# Heater_Driver.net
KiCad netlist of a schematic drawn in Altium Designer
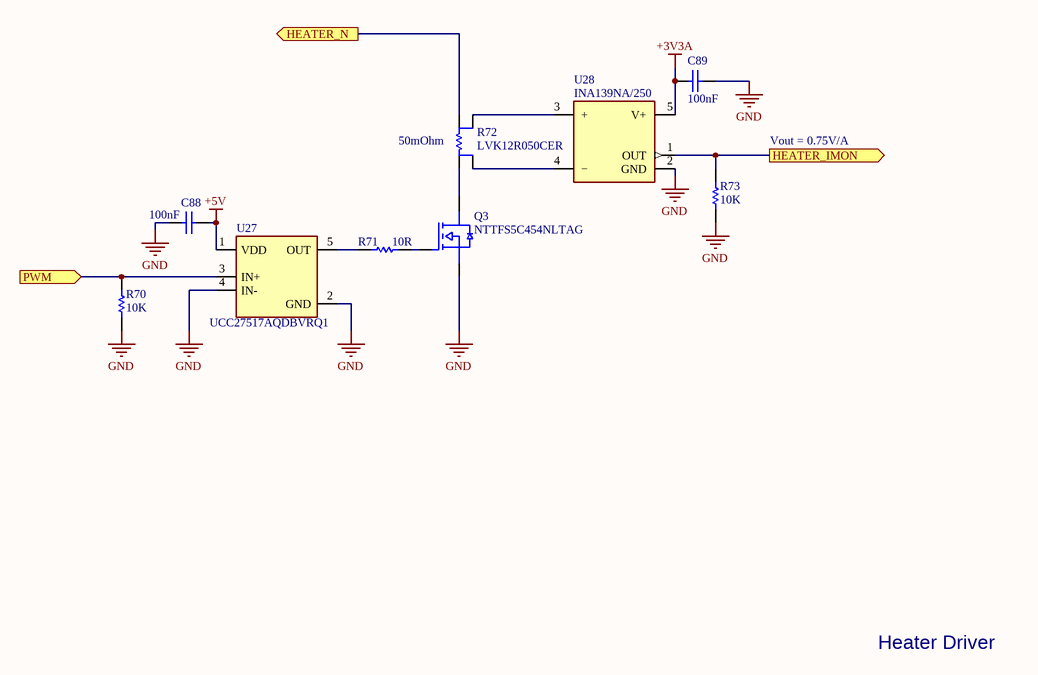
[diagram p0: Heater_Driver.SchDoc]

(export (version "E")
  (design (tool "Eeschema 10.0.6"))
  (components
    (comp (ref "C88")
      (value "C0603C104K5RACTU")
      (footprint "CAPC0603X040")
      (description "0.1 µF ±10% 50V Ceramic Capacitor X7R 0603 (1608 Metric)")
      (fields
        (field (name "TOLERANCE") "10%")
        (field (name "DISTRIBUTOR PART NUMBER") "399-C0603C104K5RACTUCT-ND")
        (field (name "CAPACITANCE") "100nF")
      )
      (libsource (lib "Ahristi_Library") (part "C0603C104K5RACTU"))
    )
    (comp (ref "C89")
      (value "C0603C104K5RACTU")
      (footprint "CAPC0603X040")
      (description "0.1 µF ±10% 50V Ceramic Capacitor X7R 0603 (1608 Metric)")
      (fields
        (field (name "TOLERANCE") "10%")
        (field (name "DISTRIBUTOR PART NUMBER") "399-C0603C104K5RACTUCT-ND")
        (field (name "CAPACITANCE") "100nF")
      )
      (libsource (lib "Ahristi_Library") (part "C0603C104K5RACTU"))
    )
    (comp (ref "Q3")
      (value "NTTFS5C454NLTAG")
      (footprint "NTTFS5C454NLTAG")
      (description "N-MOSFET 40 V , 85 A, 3.8 mΩ Rds(on) @ 10 V, WDFN-8 3.3×3.3 mm, low Qg (~18 nC)")
      (fields
        (field (name "PART NUMBER") "NTTFS5C454NL")
        (field (name "DISTRIBUTOR PART NUMBER") "NTTFS5C454NLTAGOSCT-ND")
      )
      (libsource (lib "Ahristi_Library") (part "NTTFS5C454NLTAG"))
    )
    (comp (ref "R70")
      (value "RMCF0805FT10K0")
      (footprint "RESC0805")
      (description "10 kOhms ±1% 0.125W, 1/8W Chip Resistor 0805 (2012 Metric) Automotive AEC-Q200 Thick Film")
      (fields
        (field (name "TOLERANCE") "1%")
        (field (name "DISTRIBUTOR PART NUMBER") "RMCF0805FT10K0CT-ND")
        (field (name "RESISTANCE") "10K")
      )
      (libsource (lib "Ahristi_Library") (part "RMCF0805FT10K0"))
    )
    (comp (ref "R71")
      (value "RNCF0603AKT10R0")
      (footprint "RESC0603")
      (description "10 Ohms ±0.05% 0.1W, 1/10W Chip Resistor 0603 (1608 Metric) Automotive AEC-Q200 Thin Film")
      (fields
        (field (name "TOLERANCE") "0.05%")
        (field (name "DISTRIBUTOR PART NUMBER") "RNCF0603AKT10R0CT-ND")
        (field (name "RESISTANCE") "10R")
      )
      (libsource (lib "Ahristi_Library") (part "RESC0603"))
    )
    (comp (ref "R72")
      (value "LVK12R050CER")
      (footprint "LVK12R050CER-2")
      (description "Resistor, Current Sense 50 mOhms ±0.25% 0.5W, Moisture Resistant Thick Film")
      (fields
        (field (name "DISTRIBUTOR PART NUMBER") "273-LVK12R050CERCT-ND")
        (field (name "MANUFACTURER") "Ohmite")
        (field (name "RESISTANCE") "50mOhm")
      )
      (libsource (lib "Ahristi_Library") (part "LVK12R050CER"))
    )
    (comp (ref "R73")
      (value "RMCF0805FT10K0")
      (footprint "RESC0805")
      (description "10 kOhms ±1% 0.125W, 1/8W Chip Resistor 0805 (2012 Metric) Automotive AEC-Q200 Thick Film")
      (fields
        (field (name "TOLERANCE") "1%")
        (field (name "DISTRIBUTOR PART NUMBER") "RMCF0805FT10K0CT-ND")
        (field (name "RESISTANCE") "10K")
      )
      (libsource (lib "Ahristi_Library") (part "RMCF0805FT10K0"))
    )
    (comp (ref "U27")
      (value "UCC27517AQDBVRQ1")
      (footprint "SOT23-5 IC")
      (description "Low-Side Gate Driver IC Inverting, Non-Inverting SOT-23-5")
      (fields (field (name "DISTRIBUTOR PART NUMBER") "296-41038-1-ND"))
      (libsource (lib "Ahristi_Library") (part "UCC27517AQDBVRQ1"))
    )
    (comp (ref "U28")
      (value "INA139NA/250")
      (footprint "SOT23-5 IC")
      (description "40V Current Sense Amplifier 1 Circuit 8-MSOP")
      (fields
        (field (name "DISTRIBUTOR PART NUMBER") "INA139NA/250CT-ND")
        (field (name "PART NUMBER") "INA139NA/250")
      )
      (libsource (lib "Ahristi_Library") (part "INA139NA/250"))
    )
  )
  (nets
    (net (code "1") (name "+3V3A") (class "Default")
      (node (ref "C89") (pin "2") (pinfunction "2_2") (pintype "passive"))
      (node (ref "U28") (pin "5") (pinfunction "V+_5") (pintype "passive"))
    )
    (net (code "2") (name "+5V") (class "Default")
      (node (ref "C88") (pin "2") (pinfunction "2_2") (pintype "passive"))
      (node (ref "U27") (pin "1") (pinfunction "VDD_1") (pintype "passive"))
    )
    (net (code "3") (name "/HEATER_IMON") (class "Default")
      (node (ref "R73") (pin "2") (pinfunction "2_2") (pintype "passive"))
      (node (ref "U28") (pin "1") (pinfunction "OUT_1") (pintype "output"))
    )
    (net (code "4") (name "/HEATER_N") (class "Default")
      (node (ref "R72") (pin "1") (pinfunction "1_1") (pintype "passive"))
    )
    (net (code "5") (name "/PWM") (class "Default")
      (node (ref "R70") (pin "2") (pinfunction "2_2") (pintype "passive"))
      (node (ref "U27") (pin "3") (pinfunction "IN+_3") (pintype "passive"))
    )
    (net (code "6") (name "GND") (class "Default")
      (node (ref "C88") (pin "1") (pinfunction "1_1") (pintype "passive"))
      (node (ref "C89") (pin "1") (pinfunction "1_1") (pintype "passive"))
      (node (ref "Q3") (pin "S") (pinfunction "S_S") (pintype "passive"))
      (node (ref "R70") (pin "1") (pinfunction "1_1") (pintype "passive"))
      (node (ref "R73") (pin "1") (pinfunction "1_1") (pintype "passive"))
      (node (ref "U27") (pin "2") (pinfunction "GND_2") (pintype "passive"))
      (node (ref "U27") (pin "4") (pinfunction "IN-_4") (pintype "passive"))
      (node (ref "U28") (pin "2") (pinfunction "GND_2") (pintype "passive"))
    )
    (net (code "7") (name "Net-(Q3-PadD)") (class "Default")
      (node (ref "Q3") (pin "D") (pinfunction "D_D") (pintype "passive"))
      (node (ref "R72") (pin "4") (pinfunction "4_4") (pintype "passive"))
    )
    (net (code "8") (name "Net-(Q3-PadG)") (class "Default")
      (node (ref "Q3") (pin "G") (pinfunction "G_G") (pintype "passive"))
      (node (ref "R71") (pin "2") (pinfunction "2_2") (pintype "passive"))
    )
    (net (code "9") (name "Net-(U27-OUT)") (class "Default")
      (node (ref "R71") (pin "1") (pinfunction "1_1") (pintype "passive"))
      (node (ref "U27") (pin "5") (pinfunction "OUT_5") (pintype "passive"))
    )
    (net (code "10") (name "Net-(U28-+)") (class "Default")
      (node (ref "R72") (pin "2") (pinfunction "2_2") (pintype "passive"))
      (node (ref "U28") (pin "3") (pinfunction "+_3") (pintype "passive"))
    )
    (net (code "11") (name "Net-(U28-−)") (class "Default")
      (node (ref "R72") (pin "3") (pinfunction "3_3") (pintype "passive"))
      (node (ref "U28") (pin "4") (pinfunction "−_4") (pintype "passive"))
    )
  )
)
